# hc-sippy.net
KiCad netlist of a schematic drawn in EAGLE
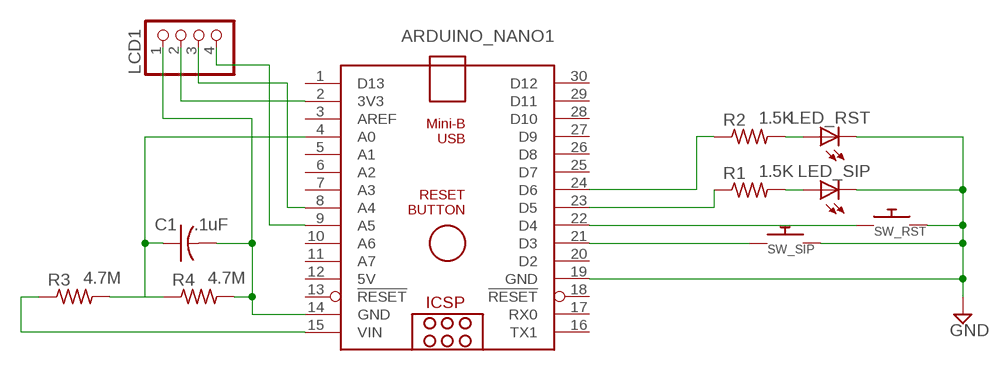
[diagram p0: schematic, sheet 1]

(export (version "E")
  (design (tool "Eeschema 10.0.6"))
  (components
    (comp (ref "ARDUINO_NANO1")
      (value "ARDUINO_NANO_HCARDUINO_NANO_NO_HOLE")
      (footprint "eagle-import:ARDUINO_NANO_NO_HOLE")
      (libsource (lib "eagle-import") (part "ARDUINO_NANO_HCARDUINO_NANO_NO_HOLE"))
    )
    (comp (ref "C1")
      (value ".1uF")
      (footprint "eagle-import:C025-050X050")
      (libsource (lib "eagle-import") (part "C-US025-050X050"))
    )
    (comp (ref "LCD1")
      (value "PINHD-1X4")
      (footprint "eagle-import:1X04")
      (libsource (lib "eagle-import") (part "PINHD-1X4"))
    )
    (comp (ref "LED_RST")
      (value "LED5MM")
      (footprint "eagle-import:LED5MM")
      (libsource (lib "eagle-import") (part "LED5MM"))
    )
    (comp (ref "LED_SIP")
      (value "LED5MM")
      (footprint "eagle-import:LED5MM")
      (libsource (lib "eagle-import") (part "LED5MM"))
    )
    (comp (ref "R1")
      (value "1.5K")
      (footprint "eagle-import:0309_12")
      (libsource (lib "eagle-import") (part "R-US_0309/12"))
    )
    (comp (ref "R2")
      (value "1.5K")
      (footprint "eagle-import:0309_12")
      (libsource (lib "eagle-import") (part "R-US_0309/12"))
    )
    (comp (ref "R3")
      (value "4.7M")
      (footprint "eagle-import:0309_12")
      (libsource (lib "eagle-import") (part "R-US_0309/12"))
    )
    (comp (ref "R4")
      (value "4.7M")
      (footprint "eagle-import:0309_12")
      (libsource (lib "eagle-import") (part "R-US_0309/12"))
    )
    (comp (ref "SW_RST")
      (value "SWITCH_PUSHBUTTONEVQ-PE")
      (footprint "eagle-import:TACT_PANA-EVQ")
      (libsource (lib "eagle-import") (part "SWITCH_PUSHBUTTONEVQ-PE"))
    )
    (comp (ref "SW_SIP")
      (value "SWITCH_PUSHBUTTONEVQ-PE")
      (footprint "eagle-import:TACT_PANA-EVQ")
      (libsource (lib "eagle-import") (part "SWITCH_PUSHBUTTONEVQ-PE"))
    )
  )
  (nets
    (net (code "1") (name "/5V") (class "Default")
      (node (ref "ARDUINO_NANO1") (pin "12") (pinfunction "5V_12") (pintype "power_in"))
    )
    (net (code "2") (name "GND") (class "Default")
      (node (ref "ARDUINO_NANO1") (pin "19") (pinfunction "GND_19") (pintype "power_in"))
      (node (ref "LED_RST") (pin "K") (pinfunction "C_K") (pintype "passive"))
      (node (ref "LED_SIP") (pin "K") (pinfunction "C_K") (pintype "passive"))
      (node (ref "SW_RST") (pin "P$2") (pinfunction "P$2_P$2") (pintype "passive"))
      (node (ref "SW_SIP") (pin "P$2") (pinfunction "P$2_P$2") (pintype "passive"))
    )
    (net (code "3") (name "Net-(ARDUINO_NANO1-3V3)") (class "Default")
      (node (ref "ARDUINO_NANO1") (pin "2") (pinfunction "3V3_2") (pintype "output"))
      (node (ref "LCD1") (pin "2") (pinfunction "2_2") (pintype "passive"))
    )
    (net (code "4") (name "Net-(ARDUINO_NANO1-A0)") (class "Default")
      (node (ref "ARDUINO_NANO1") (pin "4") (pinfunction "A0_4") (pintype "bidirectional"))
      (node (ref "C1") (pin "1") (pinfunction "1_1") (pintype "passive"))
      (node (ref "R3") (pin "2") (pinfunction "2_2") (pintype "passive"))
      (node (ref "R4") (pin "1") (pinfunction "1_1") (pintype "passive"))
    )
    (net (code "5") (name "Net-(ARDUINO_NANO1-A4)") (class "Default")
      (node (ref "ARDUINO_NANO1") (pin "8") (pinfunction "A4_8") (pintype "bidirectional"))
      (node (ref "LCD1") (pin "3") (pinfunction "3_3") (pintype "passive"))
    )
    (net (code "6") (name "Net-(ARDUINO_NANO1-A5)") (class "Default")
      (node (ref "ARDUINO_NANO1") (pin "9") (pinfunction "A5_9") (pintype "bidirectional"))
      (node (ref "LCD1") (pin "4") (pinfunction "4_4") (pintype "passive"))
    )
    (net (code "7") (name "Net-(ARDUINO_NANO1-D3)") (class "Default")
      (node (ref "ARDUINO_NANO1") (pin "21") (pinfunction "D3_21") (pintype "bidirectional"))
      (node (ref "SW_SIP") (pin "P$1") (pinfunction "P$1_P$1") (pintype "passive"))
    )
    (net (code "8") (name "Net-(ARDUINO_NANO1-D4)") (class "Default")
      (node (ref "ARDUINO_NANO1") (pin "22") (pinfunction "D4_22") (pintype "bidirectional"))
      (node (ref "SW_RST") (pin "P$1") (pinfunction "P$1_P$1") (pintype "passive"))
    )
    (net (code "9") (name "Net-(ARDUINO_NANO1-D5)") (class "Default")
      (node (ref "ARDUINO_NANO1") (pin "23") (pinfunction "D5_23") (pintype "bidirectional"))
      (node (ref "R1") (pin "1") (pinfunction "1_1") (pintype "passive"))
    )
    (net (code "10") (name "Net-(ARDUINO_NANO1-D6)") (class "Default")
      (node (ref "ARDUINO_NANO1") (pin "24") (pinfunction "D6_24") (pintype "bidirectional"))
      (node (ref "R2") (pin "1") (pinfunction "1_1") (pintype "passive"))
    )
    (net (code "11") (name "Net-(ARDUINO_NANO1-GND-Pad14)") (class "Default")
      (node (ref "ARDUINO_NANO1") (pin "14") (pinfunction "GND_14") (pintype "power_in"))
      (node (ref "C1") (pin "2") (pinfunction "2_2") (pintype "passive"))
      (node (ref "LCD1") (pin "1") (pinfunction "1_1") (pintype "passive"))
      (node (ref "R4") (pin "2") (pinfunction "2_2") (pintype "passive"))
    )
    (net (code "12") (name "Net-(ARDUINO_NANO1-VIN)") (class "Default")
      (node (ref "ARDUINO_NANO1") (pin "15") (pinfunction "VIN_15") (pintype "power_in"))
      (node (ref "R3") (pin "1") (pinfunction "1_1") (pintype "passive"))
    )
    (net (code "13") (name "Net-(LED_RST-PadA)") (class "Default")
      (node (ref "LED_RST") (pin "A") (pinfunction "A_A") (pintype "passive"))
      (node (ref "R2") (pin "2") (pinfunction "2_2") (pintype "passive"))
    )
    (net (code "14") (name "Net-(LED_SIP-PadA)") (class "Default")
      (node (ref "LED_SIP") (pin "A") (pinfunction "A_A") (pintype "passive"))
      (node (ref "R1") (pin "2") (pinfunction "2_2") (pintype "passive"))
    )
    (net (code "15") (name "unconnected-(ARDUINO_NANO1-A1-Pad5)") (class "Default")
      (node (ref "ARDUINO_NANO1") (pin "5") (pinfunction "A1_5") (pintype "bidirectional"))
    )
    (net (code "16") (name "unconnected-(ARDUINO_NANO1-A2-Pad6)") (class "Default")
      (node (ref "ARDUINO_NANO1") (pin "6") (pinfunction "A2_6") (pintype "bidirectional"))
    )
    (net (code "17") (name "unconnected-(ARDUINO_NANO1-A3-Pad7)") (class "Default")
      (node (ref "ARDUINO_NANO1") (pin "7") (pinfunction "A3_7") (pintype "bidirectional"))
    )
    (net (code "18") (name "unconnected-(ARDUINO_NANO1-A6-Pad10)") (class "Default")
      (node (ref "ARDUINO_NANO1") (pin "10") (pinfunction "A6_10") (pintype "bidirectional"))
    )
    (net (code "19") (name "unconnected-(ARDUINO_NANO1-A7-Pad11)") (class "Default")
      (node (ref "ARDUINO_NANO1") (pin "11") (pinfunction "A7_11") (pintype "bidirectional"))
    )
    (net (code "20") (name "unconnected-(ARDUINO_NANO1-AREF-Pad3)") (class "Default")
      (node (ref "ARDUINO_NANO1") (pin "3") (pinfunction "AREF_3") (pintype "input"))
    )
    (net (code "21") (name "unconnected-(ARDUINO_NANO1-D2-Pad20)") (class "Default")
      (node (ref "ARDUINO_NANO1") (pin "20") (pinfunction "D2_20") (pintype "bidirectional"))
    )
    (net (code "22") (name "unconnected-(ARDUINO_NANO1-D7-Pad25)") (class "Default")
      (node (ref "ARDUINO_NANO1") (pin "25") (pinfunction "D7_25") (pintype "bidirectional"))
    )
    (net (code "23") (name "unconnected-(ARDUINO_NANO1-D8-Pad26)") (class "Default")
      (node (ref "ARDUINO_NANO1") (pin "26") (pinfunction "D8_26") (pintype "bidirectional"))
    )
    (net (code "24") (name "unconnected-(ARDUINO_NANO1-D9-Pad27)") (class "Default")
      (node (ref "ARDUINO_NANO1") (pin "27") (pinfunction "D9_27") (pintype "bidirectional"))
    )
    (net (code "25") (name "unconnected-(ARDUINO_NANO1-D10-Pad28)") (class "Default")
      (node (ref "ARDUINO_NANO1") (pin "28") (pinfunction "D10_28") (pintype "bidirectional"))
    )
    (net (code "26") (name "unconnected-(ARDUINO_NANO1-D11-Pad29)") (class "Default")
      (node (ref "ARDUINO_NANO1") (pin "29") (pinfunction "D11_29") (pintype "bidirectional"))
    )
    (net (code "27") (name "unconnected-(ARDUINO_NANO1-D12-Pad30)") (class "Default")
      (node (ref "ARDUINO_NANO1") (pin "30") (pinfunction "D12_30") (pintype "bidirectional"))
    )
    (net (code "28") (name "unconnected-(ARDUINO_NANO1-D13-Pad1)") (class "Default")
      (node (ref "ARDUINO_NANO1") (pin "1") (pinfunction "D13_1") (pintype "bidirectional"))
    )
    (net (code "29") (name "unconnected-(ARDUINO_NANO1-RX0-Pad17)") (class "Default")
      (node (ref "ARDUINO_NANO1") (pin "17") (pinfunction "RX0_17") (pintype "bidirectional"))
    )
    (net (code "30") (name "unconnected-(ARDUINO_NANO1-TX1-Pad16)") (class "Default")
      (node (ref "ARDUINO_NANO1") (pin "16") (pinfunction "TX1_16") (pintype "bidirectional"))
    )
    (net (code "31") (name "unconnected-(ARDUINO_NANO1-~{RESET}-Pad13)") (class "Default")
      (node (ref "ARDUINO_NANO1") (pin "13") (pinfunction "~{RESET}_13") (pintype "input"))
    )
    (net (code "32") (name "unconnected-(ARDUINO_NANO1-~{RESET}-Pad18)") (class "Default")
      (node (ref "ARDUINO_NANO1") (pin "18") (pinfunction "~{RESET}_18") (pintype "input"))
    )
  )
)
